# source_eagle.net
KiCad netlist of a schematic drawn in EAGLE
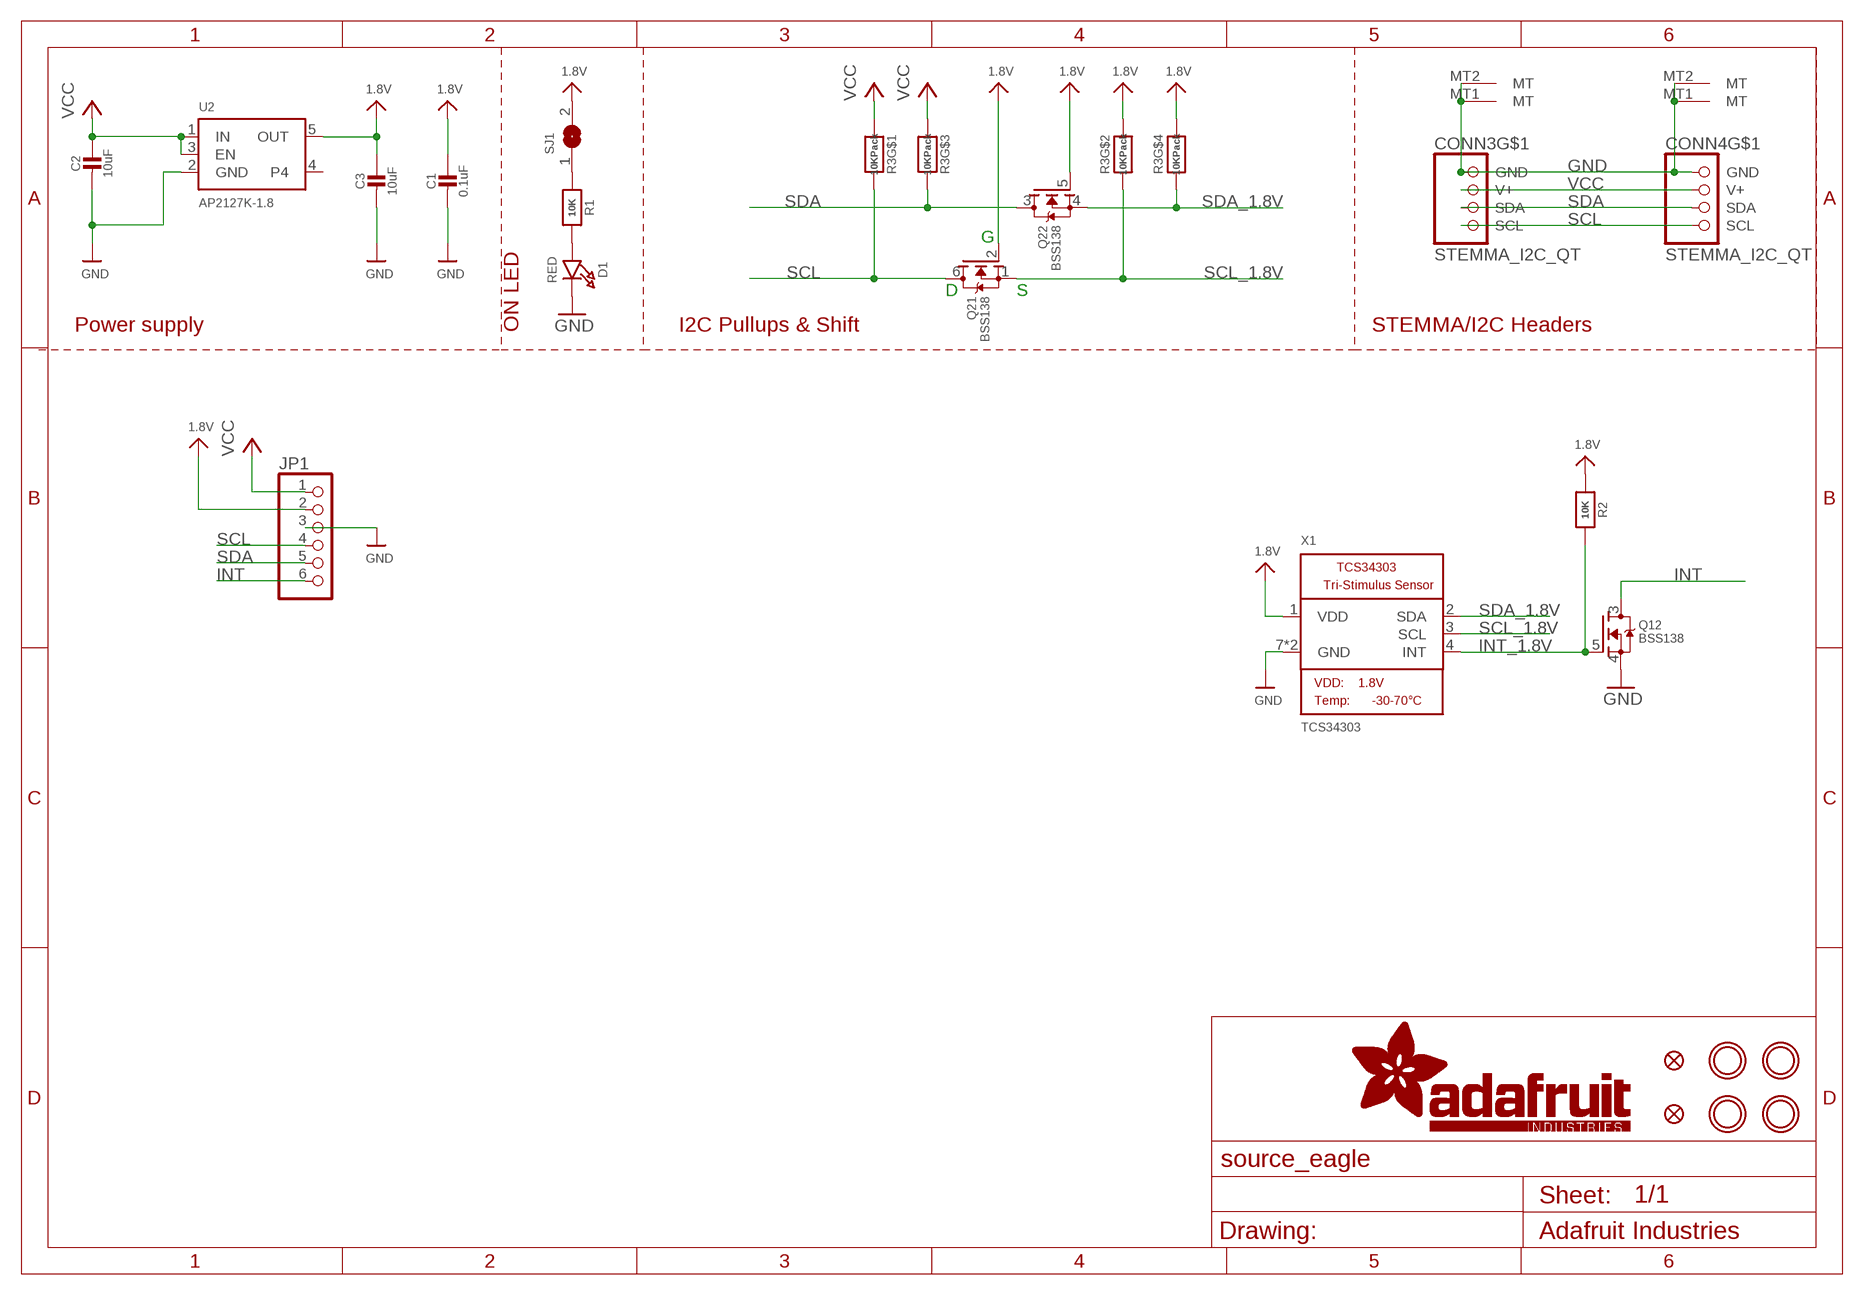
[diagram p0: schematic, sheet 1]

(export (version "E")
  (design (tool "Eeschema 10.0.6"))
  (components
    (comp (ref "C1")
      (value "0.1uF")
      (footprint "eagle-import:0603-NO")
      (libsource (lib "eagle-import") (part "CAP_CERAMIC0603_NO"))
    )
    (comp (ref "C2")
      (value "10uF")
      (footprint "eagle-import:0805-NO")
      (libsource (lib "eagle-import") (part "CAP_CERAMIC0805-NOOUTLINE"))
    )
    (comp (ref "C3")
      (value "10uF")
      (footprint "eagle-import:0805-NO")
      (libsource (lib "eagle-import") (part "CAP_CERAMIC0805-NOOUTLINE"))
    )
    (comp (ref "CONN3")
      (value "STEMMA_I2C_QT")
      (footprint "eagle-import:JST_SH4")
      (libsource (lib "eagle-import") (part "STEMMA_I2C_QT"))
    )
    (comp (ref "CONN4")
      (value "STEMMA_I2C_QT")
      (footprint "eagle-import:JST_SH4")
      (libsource (lib "eagle-import") (part "STEMMA_I2C_QT"))
    )
    (comp (ref "D1")
      (value "RED")
      (footprint "eagle-import:CHIPLED_0603_NOOUTLINE")
      (libsource (lib "eagle-import") (part "LED0603_NOOUTLINE"))
    )
    (comp (ref "FID3")
      (value "FIDUCIAL_0.5MM")
      (footprint "eagle-import:FIDUCIAL_0.5MM")
      (libsource (lib "eagle-import") (part "FIDUCIAL_0.5MM"))
    )
    (comp (ref "FID4")
      (value "FIDUCIAL_0.5MM")
      (footprint "eagle-import:FIDUCIAL_0.5MM")
      (libsource (lib "eagle-import") (part "FIDUCIAL_0.5MM"))
    )
    (comp (ref "JP1")
      (value "HEADER-1X670MIL")
      (footprint "eagle-import:1X06_ROUND_70")
      (libsource (lib "eagle-import") (part "HEADER-1X670MIL"))
    )
    (comp (ref "Q1")
      (value "BSS138")
      (footprint "eagle-import:SOT363")
      (libsource (lib "eagle-import") (part "MOSFET-N_DUAL"))
    )
    (comp (ref "Q2")
      (value "BSS138")
      (footprint "eagle-import:SOT363")
      (libsource (lib "eagle-import") (part "MOSFET-N_DUAL"))
    )
    (comp (ref "R1")
      (value "10K")
      (footprint "eagle-import:0603-NO")
      (libsource (lib "eagle-import") (part "RESISTOR_0603_NOOUT"))
    )
    (comp (ref "R2")
      (value "10K")
      (footprint "eagle-import:0603-NO")
      (libsource (lib "eagle-import") (part "RESISTOR_0603_NOOUT"))
    )
    (comp (ref "R3")
      (value "10KPack")
      (footprint "eagle-import:RESPACK_4X0603")
      (libsource (lib "eagle-import") (part "RESISTOR_4PACK"))
    )
    (comp (ref "SJ1")
      (value "SOLDERJUMPERCLOSED")
      (footprint "eagle-import:SOLDERJUMPER_CLOSEDWIRE")
      (libsource (lib "eagle-import") (part "SOLDERJUMPERCLOSED"))
    )
    (comp (ref "U$1")
      (value "MOUNTINGHOLE2.5")
      (footprint "eagle-import:MOUNTINGHOLE_2.5_PLATED")
      (libsource (lib "eagle-import") (part "MOUNTINGHOLE2.5"))
    )
    (comp (ref "U$9")
      (value "MOUNTINGHOLE2.5")
      (footprint "eagle-import:MOUNTINGHOLE_2.5_PLATED")
      (libsource (lib "eagle-import") (part "MOUNTINGHOLE2.5"))
    )
    (comp (ref "U$17")
      (value "MOUNTINGHOLE2.5")
      (footprint "eagle-import:MOUNTINGHOLE_2.5_PLATED")
      (libsource (lib "eagle-import") (part "MOUNTINGHOLE2.5"))
    )
    (comp (ref "U$20")
      (value "MOUNTINGHOLE2.5")
      (footprint "eagle-import:MOUNTINGHOLE_2.5_PLATED")
      (libsource (lib "eagle-import") (part "MOUNTINGHOLE2.5"))
    )
    (comp (ref "U2")
      (value "AP2127K-1.8")
      (footprint "eagle-import:SOT23-5")
      (libsource (lib "eagle-import") (part "VREG_SOT23-5"))
    )
    (comp (ref "X1")
      (value "TCS34303")
      (footprint "eagle-import:TCS34303")
      (libsource (lib "eagle-import") (part "TCS34303"))
    )
  )
  (nets
    (net (code "1") (name "/INT") (class "Default")
      (node (ref "JP1") (pin "6") (pinfunction "6_6") (pintype "passive"))
      (node (ref "Q1") (pin "3") (pinfunction "D_3") (pintype "bidirectional"))
    )
    (net (code "2") (name "/INT_1.8V") (class "Default")
      (node (ref "Q1") (pin "5") (pinfunction "G_5") (pintype "bidirectional"))
      (node (ref "R2") (pin "2") (pinfunction "2_2") (pintype "passive"))
      (node (ref "X1") (pin "4") (pinfunction "INT_4") (pintype "output"))
    )
    (net (code "3") (name "/SCL") (class "Default")
      (node (ref "CONN3") (pin "4") (pinfunction "SCL_4") (pintype "passive"))
      (node (ref "CONN4") (pin "4") (pinfunction "SCL_4") (pintype "passive"))
      (node (ref "JP1") (pin "4") (pinfunction "4_4") (pintype "passive"))
      (node (ref "Q2") (pin "6") (pinfunction "D_6") (pintype "bidirectional"))
      (node (ref "R3") (pin "8") (pinfunction "2_8") (pintype "passive"))
    )
    (net (code "4") (name "/SCL_1.8V") (class "Default")
      (node (ref "Q2") (pin "1") (pinfunction "S_1") (pintype "bidirectional"))
      (node (ref "R3") (pin "7") (pinfunction "2_7") (pintype "passive"))
      (node (ref "X1") (pin "3") (pinfunction "SCL_3") (pintype "bidirectional"))
    )
    (net (code "5") (name "/SDA") (class "Default")
      (node (ref "CONN3") (pin "3") (pinfunction "SDA_3") (pintype "passive"))
      (node (ref "CONN4") (pin "3") (pinfunction "SDA_3") (pintype "passive"))
      (node (ref "JP1") (pin "5") (pinfunction "5_5") (pintype "passive"))
      (node (ref "Q2") (pin "3") (pinfunction "D_3") (pintype "bidirectional"))
      (node (ref "R3") (pin "6") (pinfunction "2_6") (pintype "passive"))
    )
    (net (code "6") (name "/SDA_1.8V") (class "Default")
      (node (ref "Q2") (pin "4") (pinfunction "S_4") (pintype "bidirectional"))
      (node (ref "R3") (pin "5") (pinfunction "2_5") (pintype "passive"))
      (node (ref "X1") (pin "2") (pinfunction "SDA_2") (pintype "bidirectional"))
    )
    (net (code "7") (name "1.8V") (class "Default")
      (node (ref "C1") (pin "1") (pinfunction "1_1") (pintype "passive"))
      (node (ref "C3") (pin "1") (pinfunction "1_1") (pintype "passive"))
      (node (ref "JP1") (pin "2") (pinfunction "2_2") (pintype "passive"))
      (node (ref "Q2") (pin "2") (pinfunction "G_2") (pintype "bidirectional"))
      (node (ref "Q2") (pin "5") (pinfunction "G_5") (pintype "bidirectional"))
      (node (ref "R2") (pin "1") (pinfunction "1_1") (pintype "passive"))
      (node (ref "R3") (pin "2") (pinfunction "1_2") (pintype "passive"))
      (node (ref "R3") (pin "4") (pinfunction "1_4") (pintype "passive"))
      (node (ref "SJ1") (pin "2") (pinfunction "2_2") (pintype "passive"))
      (node (ref "U2") (pin "5") (pinfunction "OUT_5") (pintype "power_in"))
      (node (ref "X1") (pin "1") (pinfunction "VDD_1") (pintype "power_in"))
    )
    (net (code "8") (name "GND") (class "Default")
      (node (ref "C1") (pin "2") (pinfunction "2_2") (pintype "passive"))
      (node (ref "C2") (pin "2") (pinfunction "2_2") (pintype "passive"))
      (node (ref "C3") (pin "2") (pinfunction "2_2") (pintype "passive"))
      (node (ref "CONN3") (pin "1") (pinfunction "GND_1") (pintype "passive"))
      (node (ref "CONN3") (pin "MT1") (pinfunction "MT_MT1") (pintype "bidirectional"))
      (node (ref "CONN3") (pin "MT2") (pinfunction "MT_MT2") (pintype "bidirectional"))
      (node (ref "CONN4") (pin "1") (pinfunction "GND_1") (pintype "passive"))
      (node (ref "CONN4") (pin "MT1") (pinfunction "MT_MT1") (pintype "bidirectional"))
      (node (ref "CONN4") (pin "MT2") (pinfunction "MT_MT2") (pintype "bidirectional"))
      (node (ref "D1") (pin "C") (pinfunction "C_C") (pintype "passive"))
      (node (ref "JP1") (pin "3") (pinfunction "3_3") (pintype "passive"))
      (node (ref "Q1") (pin "4") (pinfunction "S_4") (pintype "bidirectional"))
      (node (ref "U2") (pin "2") (pinfunction "GND_2") (pintype "power_in"))
      (node (ref "X1") (pin "7") (pinfunction "GND_7") (pintype "power_in"))
      (node (ref "X1") (pin "8") (pinfunction "GND_8") (pintype "power_in"))
    )
    (net (code "9") (name "Net-(D1-PadA)") (class "Default")
      (node (ref "D1") (pin "A") (pinfunction "A_A") (pintype "passive"))
      (node (ref "R1") (pin "2") (pinfunction "2_2") (pintype "passive"))
    )
    (net (code "10") (name "Net-(R1-Pad1)") (class "Default")
      (node (ref "R1") (pin "1") (pinfunction "1_1") (pintype "passive"))
      (node (ref "SJ1") (pin "1") (pinfunction "1_1") (pintype "passive"))
    )
    (net (code "11") (name "VCC") (class "Default")
      (node (ref "C2") (pin "1") (pinfunction "1_1") (pintype "passive"))
      (node (ref "CONN3") (pin "2") (pinfunction "V+_2") (pintype "passive"))
      (node (ref "CONN4") (pin "2") (pinfunction "V+_2") (pintype "passive"))
      (node (ref "JP1") (pin "1") (pinfunction "1_1") (pintype "passive"))
      (node (ref "R3") (pin "1") (pinfunction "1_1") (pintype "passive"))
      (node (ref "R3") (pin "3") (pinfunction "1_3") (pintype "passive"))
      (node (ref "U2") (pin "1") (pinfunction "IN_1") (pintype "power_in"))
      (node (ref "U2") (pin "3") (pinfunction "EN_3") (pintype "input"))
    )
    (net (code "12") (name "unconnected-(U2-P4-Pad4)") (class "Default")
      (node (ref "U2") (pin "4") (pinfunction "P4_4") (pintype "bidirectional"))
    )
  )
)
